# B133X.net
KiCad netlist of a schematic drawn in EAGLE
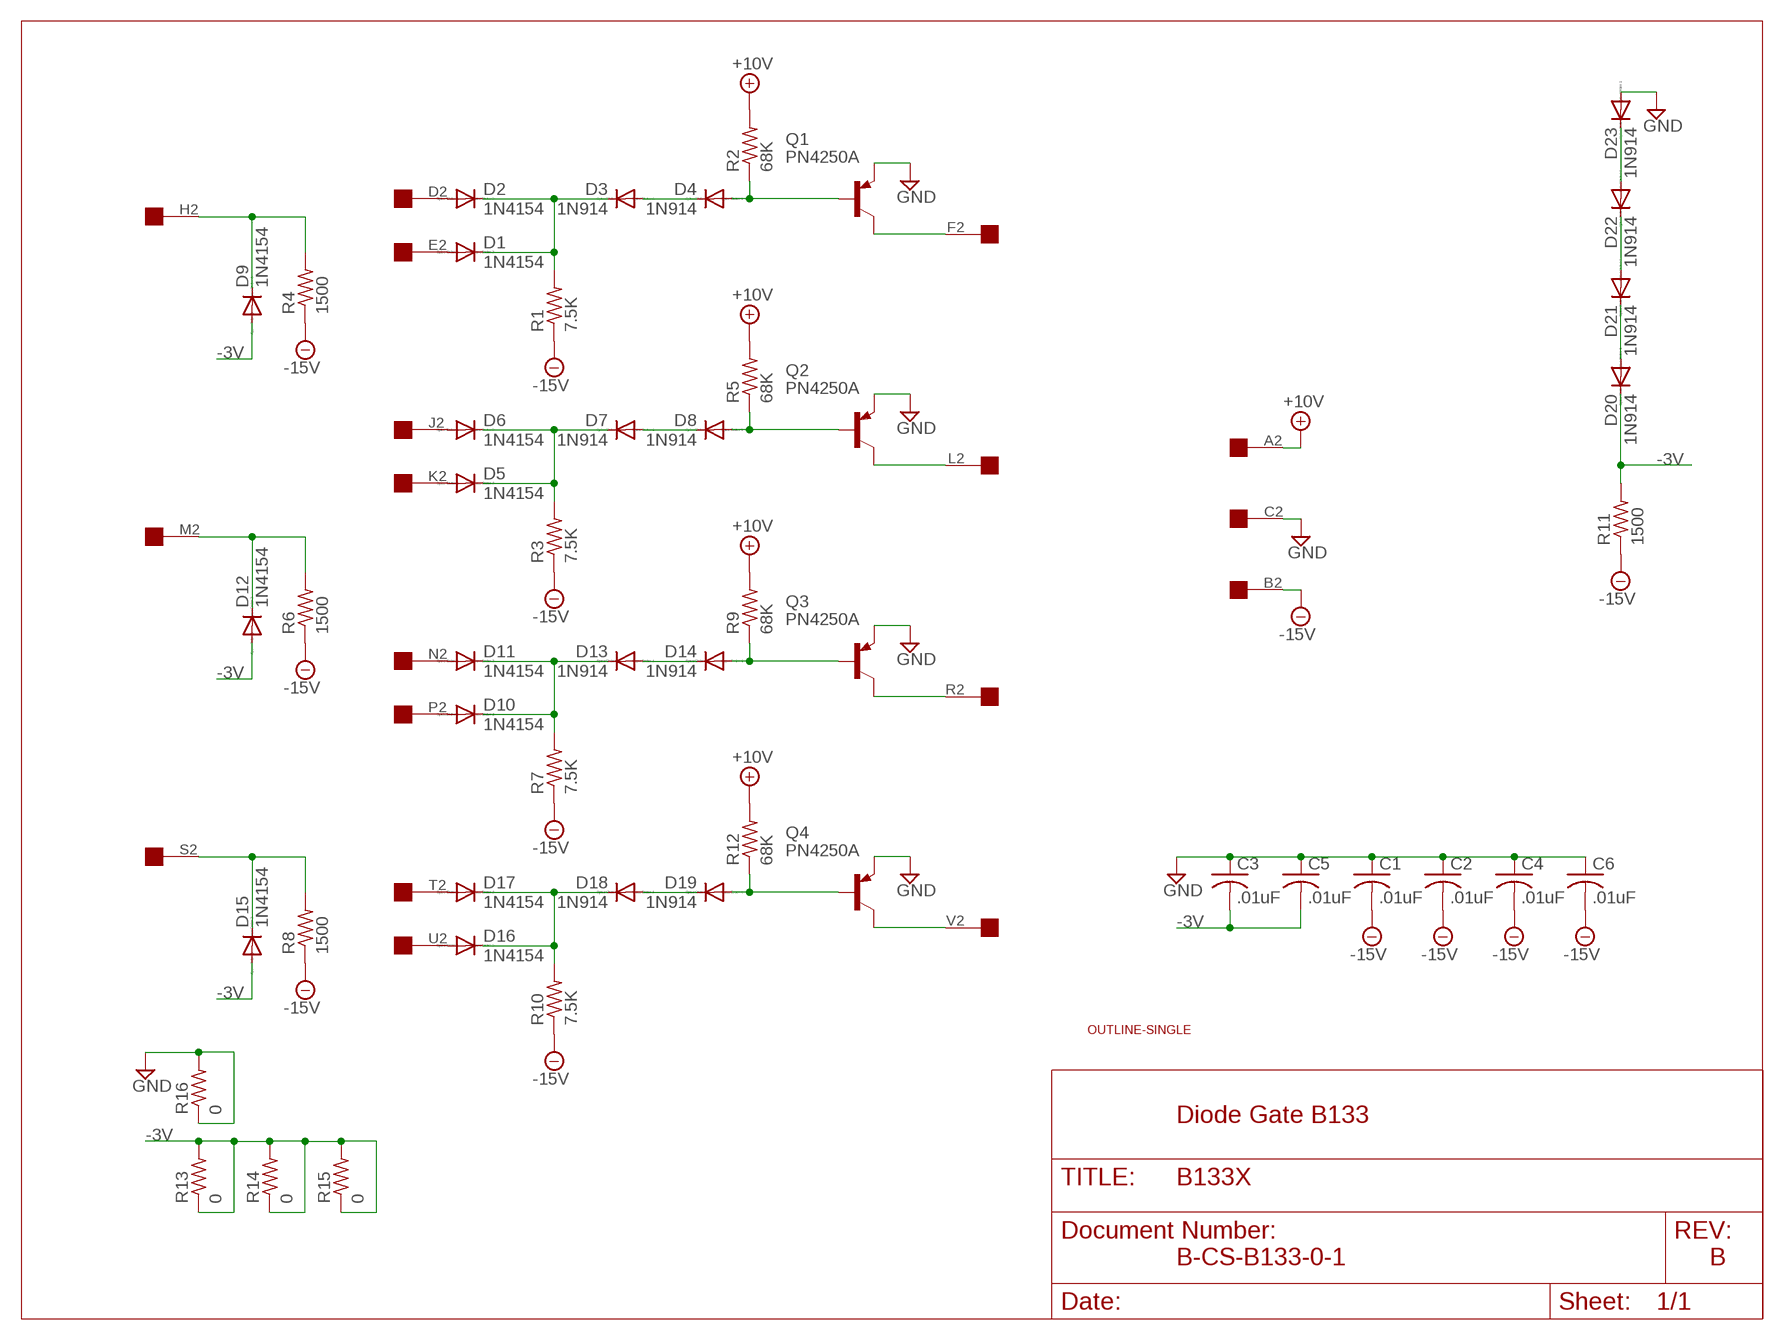
[diagram p0: schematic, sheet 1]

(export (version "E")
  (design (tool "Eeschema 10.0.6"))
  (components
    (comp (ref "C1")
      (value ".01uF")
      (footprint "eagle-import:C063-025X075")
      (libsource (lib "eagle-import") (part "C-US"))
    )
    (comp (ref "C2")
      (value ".01uF")
      (footprint "eagle-import:C063-025X075")
      (libsource (lib "eagle-import") (part "C-US"))
    )
    (comp (ref "C3")
      (value ".01uF")
      (footprint "eagle-import:C063-025X075")
      (libsource (lib "eagle-import") (part "C-US"))
    )
    (comp (ref "C4")
      (value ".01uF")
      (footprint "eagle-import:C063-025X075")
      (libsource (lib "eagle-import") (part "C-US"))
    )
    (comp (ref "C5")
      (value ".01uF")
      (footprint "eagle-import:C063-025X075")
      (libsource (lib "eagle-import") (part "C-US"))
    )
    (comp (ref "C6")
      (value ".01uF")
      (footprint "eagle-import:C063-025X075")
      (libsource (lib "eagle-import") (part "C-US"))
    )
    (comp (ref "D1")
      (value "1N4154")
      (footprint "eagle-import:DO35-10")
      (libsource (lib "eagle-import") (part "DIODE-DO35-10"))
    )
    (comp (ref "D2")
      (value "1N4154")
      (footprint "eagle-import:DO35-10")
      (libsource (lib "eagle-import") (part "DIODE-DO35-10"))
    )
    (comp (ref "D3")
      (value "1N914")
      (footprint "eagle-import:DO35-10")
      (libsource (lib "eagle-import") (part "DIODE-DO35-10"))
    )
    (comp (ref "D4")
      (value "1N914")
      (footprint "eagle-import:DO35-10")
      (libsource (lib "eagle-import") (part "DIODE-DO35-10"))
    )
    (comp (ref "D5")
      (value "1N4154")
      (footprint "eagle-import:DO35-10")
      (libsource (lib "eagle-import") (part "DIODE-DO35-10"))
    )
    (comp (ref "D6")
      (value "1N4154")
      (footprint "eagle-import:DO35-10")
      (libsource (lib "eagle-import") (part "DIODE-DO35-10"))
    )
    (comp (ref "D7")
      (value "1N914")
      (footprint "eagle-import:DO35-10")
      (libsource (lib "eagle-import") (part "DIODE-DO35-10"))
    )
    (comp (ref "D8")
      (value "1N914")
      (footprint "eagle-import:DO35-10")
      (libsource (lib "eagle-import") (part "DIODE-DO35-10"))
    )
    (comp (ref "D9")
      (value "1N4154")
      (footprint "eagle-import:DO35-10")
      (libsource (lib "eagle-import") (part "DIODE-DO35-10"))
    )
    (comp (ref "D10")
      (value "1N4154")
      (footprint "eagle-import:DO35-10")
      (libsource (lib "eagle-import") (part "DIODE-DO35-10"))
    )
    (comp (ref "D11")
      (value "1N4154")
      (footprint "eagle-import:DO35-10")
      (libsource (lib "eagle-import") (part "DIODE-DO35-10"))
    )
    (comp (ref "D12")
      (value "1N4154")
      (footprint "eagle-import:DO35-10")
      (libsource (lib "eagle-import") (part "DIODE-DO35-10"))
    )
    (comp (ref "D13")
      (value "1N914")
      (footprint "eagle-import:DO35-10")
      (libsource (lib "eagle-import") (part "DIODE-DO35-10"))
    )
    (comp (ref "D14")
      (value "1N914")
      (footprint "eagle-import:DO35-10")
      (libsource (lib "eagle-import") (part "DIODE-DO35-10"))
    )
    (comp (ref "D15")
      (value "1N4154")
      (footprint "eagle-import:DO35-10")
      (libsource (lib "eagle-import") (part "DIODE-DO35-10"))
    )
    (comp (ref "D16")
      (value "1N4154")
      (footprint "eagle-import:DO35-10")
      (libsource (lib "eagle-import") (part "DIODE-DO35-10"))
    )
    (comp (ref "D17")
      (value "1N4154")
      (footprint "eagle-import:DO35-10")
      (libsource (lib "eagle-import") (part "DIODE-DO35-10"))
    )
    (comp (ref "D18")
      (value "1N914")
      (footprint "eagle-import:DO35-10")
      (libsource (lib "eagle-import") (part "DIODE-DO35-10"))
    )
    (comp (ref "D19")
      (value "1N914")
      (footprint "eagle-import:DO35-10")
      (libsource (lib "eagle-import") (part "DIODE-DO35-10"))
    )
    (comp (ref "D20")
      (value "1N914")
      (footprint "eagle-import:DO35-10")
      (libsource (lib "eagle-import") (part "DIODE-DO35-10"))
    )
    (comp (ref "D21")
      (value "1N914")
      (footprint "eagle-import:DO35-10")
      (libsource (lib "eagle-import") (part "DIODE-DO35-10"))
    )
    (comp (ref "D22")
      (value "1N914")
      (footprint "eagle-import:DO35-10")
      (libsource (lib "eagle-import") (part "DIODE-DO35-10"))
    )
    (comp (ref "D23")
      (value "1N914")
      (footprint "eagle-import:DO35-10")
      (libsource (lib "eagle-import") (part "DIODE-DO35-10"))
    )
    (comp (ref "Q1")
      (value "PN4250A")
      (footprint "eagle-import:TO5")
      (libsource (lib "eagle-import") (part "-PNP-TO5"))
    )
    (comp (ref "Q2")
      (value "PN4250A")
      (footprint "eagle-import:TO5")
      (libsource (lib "eagle-import") (part "-PNP-TO5"))
    )
    (comp (ref "Q3")
      (value "PN4250A")
      (footprint "eagle-import:TO5")
      (libsource (lib "eagle-import") (part "-PNP-TO5"))
    )
    (comp (ref "Q4")
      (value "PN4250A")
      (footprint "eagle-import:TO5")
      (libsource (lib "eagle-import") (part "-PNP-TO5"))
    )
    (comp (ref "R1")
      (value "7.5K")
      (footprint "eagle-import:0207_10")
      (libsource (lib "eagle-import") (part "R-US_0207/10"))
    )
    (comp (ref "R2")
      (value "68K")
      (footprint "eagle-import:0207_10")
      (libsource (lib "eagle-import") (part "R-US_0207/10"))
    )
    (comp (ref "R3")
      (value "7.5K")
      (footprint "eagle-import:0207_10")
      (libsource (lib "eagle-import") (part "R-US_0207/10"))
    )
    (comp (ref "R4")
      (value "1500")
      (footprint "eagle-import:0207_10")
      (libsource (lib "eagle-import") (part "R-US_0207/10"))
    )
    (comp (ref "R5")
      (value "68K")
      (footprint "eagle-import:0207_10")
      (libsource (lib "eagle-import") (part "R-US_0207/10"))
    )
    (comp (ref "R6")
      (value "1500")
      (footprint "eagle-import:0207_10")
      (libsource (lib "eagle-import") (part "R-US_0207/10"))
    )
    (comp (ref "R7")
      (value "7.5K")
      (footprint "eagle-import:0207_10")
      (libsource (lib "eagle-import") (part "R-US_0207/10"))
    )
    (comp (ref "R8")
      (value "1500")
      (footprint "eagle-import:0207_10")
      (libsource (lib "eagle-import") (part "R-US_0207/10"))
    )
    (comp (ref "R9")
      (value "68K")
      (footprint "eagle-import:0207_10")
      (libsource (lib "eagle-import") (part "R-US_0207/10"))
    )
    (comp (ref "R10")
      (value "7.5K")
      (footprint "eagle-import:0207_10")
      (libsource (lib "eagle-import") (part "R-US_0207/10"))
    )
    (comp (ref "R11")
      (value "1500")
      (footprint "eagle-import:0207_10")
      (libsource (lib "eagle-import") (part "R-US_0207/10"))
    )
    (comp (ref "R12")
      (value "68K")
      (footprint "eagle-import:0207_10")
      (libsource (lib "eagle-import") (part "R-US_0207/10"))
    )
    (comp (ref "R13")
      (value "0")
      (footprint "eagle-import:0207_10")
      (libsource (lib "eagle-import") (part "R-US_0207/10"))
    )
    (comp (ref "R14")
      (value "0")
      (footprint "eagle-import:0207_10")
      (libsource (lib "eagle-import") (part "R-US_0207/10"))
    )
    (comp (ref "R15")
      (value "0")
      (footprint "eagle-import:0207_10")
      (libsource (lib "eagle-import") (part "R-US_0207/10"))
    )
    (comp (ref "R16")
      (value "0")
      (footprint "eagle-import:0207_10")
      (libsource (lib "eagle-import") (part "R-US_0207/10"))
    )
    (comp (ref "U$1")
      (value "OUTLINE-SINGLE")
      (footprint "eagle-import:SINGLE")
      (libsource (lib "eagle-import") (part "OUTLINE-SINGLE"))
    )
    (comp (ref "U$2")
      (value "EDGE-1")
      (footprint "eagle-import:EDGE-CON1")
      (libsource (lib "eagle-import") (part "EDGE-1"))
    )
  )
  (nets
    (net (code "1") (name "+10V") (class "Default")
      (node (ref "R12") (pin "2") (pinfunction "2_2") (pintype "passive"))
      (node (ref "R2") (pin "2") (pinfunction "2_2") (pintype "passive"))
      (node (ref "R5") (pin "2") (pinfunction "2_2") (pintype "passive"))
      (node (ref "R9") (pin "2") (pinfunction "2_2") (pintype "passive"))
      (node (ref "U$2") (pin "A2") (pinfunction "1_A2") (pintype "bidirectional"))
    )
    (net (code "2") (name "-15V") (class "Default")
      (node (ref "C1") (pin "2") (pinfunction "2_2") (pintype "passive"))
      (node (ref "C2") (pin "2") (pinfunction "2_2") (pintype "passive"))
      (node (ref "C4") (pin "2") (pinfunction "2_2") (pintype "passive"))
      (node (ref "C6") (pin "2") (pinfunction "2_2") (pintype "passive"))
      (node (ref "R1") (pin "1") (pinfunction "1_1") (pintype "passive"))
      (node (ref "R10") (pin "1") (pinfunction "1_1") (pintype "passive"))
      (node (ref "R11") (pin "1") (pinfunction "1_1") (pintype "passive"))
      (node (ref "R3") (pin "1") (pinfunction "1_1") (pintype "passive"))
      (node (ref "R4") (pin "1") (pinfunction "1_1") (pintype "passive"))
      (node (ref "R6") (pin "1") (pinfunction "1_1") (pintype "passive"))
      (node (ref "R7") (pin "1") (pinfunction "1_1") (pintype "passive"))
      (node (ref "R8") (pin "1") (pinfunction "1_1") (pintype "passive"))
      (node (ref "U$2") (pin "B2") (pinfunction "1_B2") (pintype "bidirectional"))
    )
    (net (code "3") (name "/-3V") (class "Default")
      (node (ref "C3") (pin "2") (pinfunction "2_2") (pintype "passive"))
      (node (ref "C5") (pin "2") (pinfunction "2_2") (pintype "passive"))
      (node (ref "D12") (pin "A") (pinfunction "A_A") (pintype "passive"))
      (node (ref "D15") (pin "A") (pinfunction "A_A") (pintype "passive"))
      (node (ref "D20") (pin "C") (pinfunction "C_C") (pintype "passive"))
      (node (ref "D9") (pin "A") (pinfunction "A_A") (pintype "passive"))
      (node (ref "R11") (pin "2") (pinfunction "2_2") (pintype "passive"))
      (node (ref "R13") (pin "1") (pinfunction "1_1") (pintype "passive"))
      (node (ref "R13") (pin "2") (pinfunction "2_2") (pintype "passive"))
      (node (ref "R14") (pin "1") (pinfunction "1_1") (pintype "passive"))
      (node (ref "R14") (pin "2") (pinfunction "2_2") (pintype "passive"))
      (node (ref "R15") (pin "1") (pinfunction "1_1") (pintype "passive"))
      (node (ref "R15") (pin "2") (pinfunction "2_2") (pintype "passive"))
    )
    (net (code "4") (name "GND") (class "Default")
      (node (ref "C1") (pin "1") (pinfunction "1_1") (pintype "passive"))
      (node (ref "C2") (pin "1") (pinfunction "1_1") (pintype "passive"))
      (node (ref "C3") (pin "1") (pinfunction "1_1") (pintype "passive"))
      (node (ref "C4") (pin "1") (pinfunction "1_1") (pintype "passive"))
      (node (ref "C5") (pin "1") (pinfunction "1_1") (pintype "passive"))
      (node (ref "C6") (pin "1") (pinfunction "1_1") (pintype "passive"))
      (node (ref "D23") (pin "A") (pinfunction "A_A") (pintype "passive"))
      (node (ref "Q1") (pin "1") (pinfunction "E_1") (pintype "passive"))
      (node (ref "Q2") (pin "1") (pinfunction "E_1") (pintype "passive"))
      (node (ref "Q3") (pin "1") (pinfunction "E_1") (pintype "passive"))
      (node (ref "Q4") (pin "1") (pinfunction "E_1") (pintype "passive"))
      (node (ref "R16") (pin "1") (pinfunction "1_1") (pintype "passive"))
      (node (ref "R16") (pin "2") (pinfunction "2_2") (pintype "passive"))
      (node (ref "U$2") (pin "C2") (pinfunction "1_C2") (pintype "bidirectional"))
    )
    (net (code "5") (name "Net-(D1-PadC)") (class "Default")
      (node (ref "D1") (pin "C") (pinfunction "C_C") (pintype "passive"))
      (node (ref "D2") (pin "C") (pinfunction "C_C") (pintype "passive"))
      (node (ref "D3") (pin "C") (pinfunction "C_C") (pintype "passive"))
      (node (ref "R1") (pin "2") (pinfunction "2_2") (pintype "passive"))
    )
    (net (code "6") (name "Net-(D3-PadA)") (class "Default")
      (node (ref "D3") (pin "A") (pinfunction "A_A") (pintype "passive"))
      (node (ref "D4") (pin "C") (pinfunction "C_C") (pintype "passive"))
    )
    (net (code "7") (name "Net-(D5-PadC)") (class "Default")
      (node (ref "D5") (pin "C") (pinfunction "C_C") (pintype "passive"))
      (node (ref "D6") (pin "C") (pinfunction "C_C") (pintype "passive"))
      (node (ref "D7") (pin "C") (pinfunction "C_C") (pintype "passive"))
      (node (ref "R3") (pin "2") (pinfunction "2_2") (pintype "passive"))
    )
    (net (code "8") (name "Net-(D7-PadA)") (class "Default")
      (node (ref "D7") (pin "A") (pinfunction "A_A") (pintype "passive"))
      (node (ref "D8") (pin "C") (pinfunction "C_C") (pintype "passive"))
    )
    (net (code "9") (name "Net-(D10-PadC)") (class "Default")
      (node (ref "D10") (pin "C") (pinfunction "C_C") (pintype "passive"))
      (node (ref "D11") (pin "C") (pinfunction "C_C") (pintype "passive"))
      (node (ref "D13") (pin "C") (pinfunction "C_C") (pintype "passive"))
      (node (ref "R7") (pin "2") (pinfunction "2_2") (pintype "passive"))
    )
    (net (code "10") (name "Net-(D13-PadA)") (class "Default")
      (node (ref "D13") (pin "A") (pinfunction "A_A") (pintype "passive"))
      (node (ref "D14") (pin "C") (pinfunction "C_C") (pintype "passive"))
    )
    (net (code "11") (name "Net-(D16-PadC)") (class "Default")
      (node (ref "D16") (pin "C") (pinfunction "C_C") (pintype "passive"))
      (node (ref "D17") (pin "C") (pinfunction "C_C") (pintype "passive"))
      (node (ref "D18") (pin "C") (pinfunction "C_C") (pintype "passive"))
      (node (ref "R10") (pin "2") (pinfunction "2_2") (pintype "passive"))
    )
    (net (code "12") (name "Net-(D18-PadA)") (class "Default")
      (node (ref "D18") (pin "A") (pinfunction "A_A") (pintype "passive"))
      (node (ref "D19") (pin "C") (pinfunction "C_C") (pintype "passive"))
    )
    (net (code "13") (name "Net-(D20-PadA)") (class "Default")
      (node (ref "D20") (pin "A") (pinfunction "A_A") (pintype "passive"))
      (node (ref "D21") (pin "C") (pinfunction "C_C") (pintype "passive"))
    )
    (net (code "14") (name "Net-(D21-PadA)") (class "Default")
      (node (ref "D21") (pin "A") (pinfunction "A_A") (pintype "passive"))
      (node (ref "D22") (pin "C") (pinfunction "C_C") (pintype "passive"))
    )
    (net (code "15") (name "Net-(D22-PadA)") (class "Default")
      (node (ref "D22") (pin "A") (pinfunction "A_A") (pintype "passive"))
      (node (ref "D23") (pin "C") (pinfunction "C_C") (pintype "passive"))
    )
    (net (code "16") (name "Net-(Q1-B)") (class "Default")
      (node (ref "D4") (pin "A") (pinfunction "A_A") (pintype "passive"))
      (node (ref "Q1") (pin "2") (pinfunction "B_2") (pintype "passive"))
      (node (ref "R2") (pin "1") (pinfunction "1_1") (pintype "passive"))
    )
    (net (code "17") (name "Net-(Q1-C)") (class "Default")
      (node (ref "Q1") (pin "3") (pinfunction "C_3") (pintype "passive"))
      (node (ref "U$2") (pin "F2") (pinfunction "1_F2") (pintype "bidirectional"))
    )
    (net (code "18") (name "Net-(Q2-B)") (class "Default")
      (node (ref "D8") (pin "A") (pinfunction "A_A") (pintype "passive"))
      (node (ref "Q2") (pin "2") (pinfunction "B_2") (pintype "passive"))
      (node (ref "R5") (pin "1") (pinfunction "1_1") (pintype "passive"))
    )
    (net (code "19") (name "Net-(Q2-C)") (class "Default")
      (node (ref "Q2") (pin "3") (pinfunction "C_3") (pintype "passive"))
      (node (ref "U$2") (pin "L2") (pinfunction "1_L2") (pintype "bidirectional"))
    )
    (net (code "20") (name "Net-(Q3-B)") (class "Default")
      (node (ref "D14") (pin "A") (pinfunction "A_A") (pintype "passive"))
      (node (ref "Q3") (pin "2") (pinfunction "B_2") (pintype "passive"))
      (node (ref "R9") (pin "1") (pinfunction "1_1") (pintype "passive"))
    )
    (net (code "21") (name "Net-(Q3-C)") (class "Default")
      (node (ref "Q3") (pin "3") (pinfunction "C_3") (pintype "passive"))
      (node (ref "U$2") (pin "R2") (pinfunction "1_R2") (pintype "bidirectional"))
    )
    (net (code "22") (name "Net-(Q4-B)") (class "Default")
      (node (ref "D19") (pin "A") (pinfunction "A_A") (pintype "passive"))
      (node (ref "Q4") (pin "2") (pinfunction "B_2") (pintype "passive"))
      (node (ref "R12") (pin "1") (pinfunction "1_1") (pintype "passive"))
    )
    (net (code "23") (name "Net-(Q4-C)") (class "Default")
      (node (ref "Q4") (pin "3") (pinfunction "C_3") (pintype "passive"))
      (node (ref "U$2") (pin "V2") (pinfunction "1_V2") (pintype "bidirectional"))
    )
    (net (code "24") (name "Net-(U$2D-1)") (class "Default")
      (node (ref "D2") (pin "A") (pinfunction "A_A") (pintype "passive"))
      (node (ref "U$2") (pin "D2") (pinfunction "1_D2") (pintype "bidirectional"))
    )
    (net (code "25") (name "Net-(U$2E-1)") (class "Default")
      (node (ref "D1") (pin "A") (pinfunction "A_A") (pintype "passive"))
      (node (ref "U$2") (pin "E2") (pinfunction "1_E2") (pintype "bidirectional"))
    )
    (net (code "26") (name "Net-(U$2G-1)") (class "Default")
      (node (ref "D9") (pin "C") (pinfunction "C_C") (pintype "passive"))
      (node (ref "R4") (pin "2") (pinfunction "2_2") (pintype "passive"))
      (node (ref "U$2") (pin "H2") (pinfunction "1_H2") (pintype "bidirectional"))
    )
    (net (code "27") (name "Net-(U$2H-1)") (class "Default")
      (node (ref "D6") (pin "A") (pinfunction "A_A") (pintype "passive"))
      (node (ref "U$2") (pin "J2") (pinfunction "1_J2") (pintype "bidirectional"))
    )
    (net (code "28") (name "Net-(U$2I-1)") (class "Default")
      (node (ref "D5") (pin "A") (pinfunction "A_A") (pintype "passive"))
      (node (ref "U$2") (pin "K2") (pinfunction "1_K2") (pintype "bidirectional"))
    )
    (net (code "29") (name "Net-(U$2K-1)") (class "Default")
      (node (ref "D12") (pin "C") (pinfunction "C_C") (pintype "passive"))
      (node (ref "R6") (pin "2") (pinfunction "2_2") (pintype "passive"))
      (node (ref "U$2") (pin "M2") (pinfunction "1_M2") (pintype "bidirectional"))
    )
    (net (code "30") (name "Net-(U$2L-1)") (class "Default")
      (node (ref "D11") (pin "A") (pinfunction "A_A") (pintype "passive"))
      (node (ref "U$2") (pin "N2") (pinfunction "1_N2") (pintype "bidirectional"))
    )
    (net (code "31") (name "Net-(U$2M-1)") (class "Default")
      (node (ref "D10") (pin "A") (pinfunction "A_A") (pintype "passive"))
      (node (ref "U$2") (pin "P2") (pinfunction "1_P2") (pintype "bidirectional"))
    )
    (net (code "32") (name "Net-(U$2O-1)") (class "Default")
      (node (ref "D15") (pin "C") (pinfunction "C_C") (pintype "passive"))
      (node (ref "R8") (pin "2") (pinfunction "2_2") (pintype "passive"))
      (node (ref "U$2") (pin "S2") (pinfunction "1_S2") (pintype "bidirectional"))
    )
    (net (code "33") (name "Net-(U$2P-1)") (class "Default")
      (node (ref "D17") (pin "A") (pinfunction "A_A") (pintype "passive"))
      (node (ref "U$2") (pin "T2") (pinfunction "1_T2") (pintype "bidirectional"))
    )
    (net (code "34") (name "Net-(U$2Q-1)") (class "Default")
      (node (ref "D16") (pin "A") (pinfunction "A_A") (pintype "passive"))
      (node (ref "U$2") (pin "U2") (pinfunction "1_U2") (pintype "bidirectional"))
    )
  )
)
